# schematic.net
KiCad netlist of a schematic drawn in EasyEDA
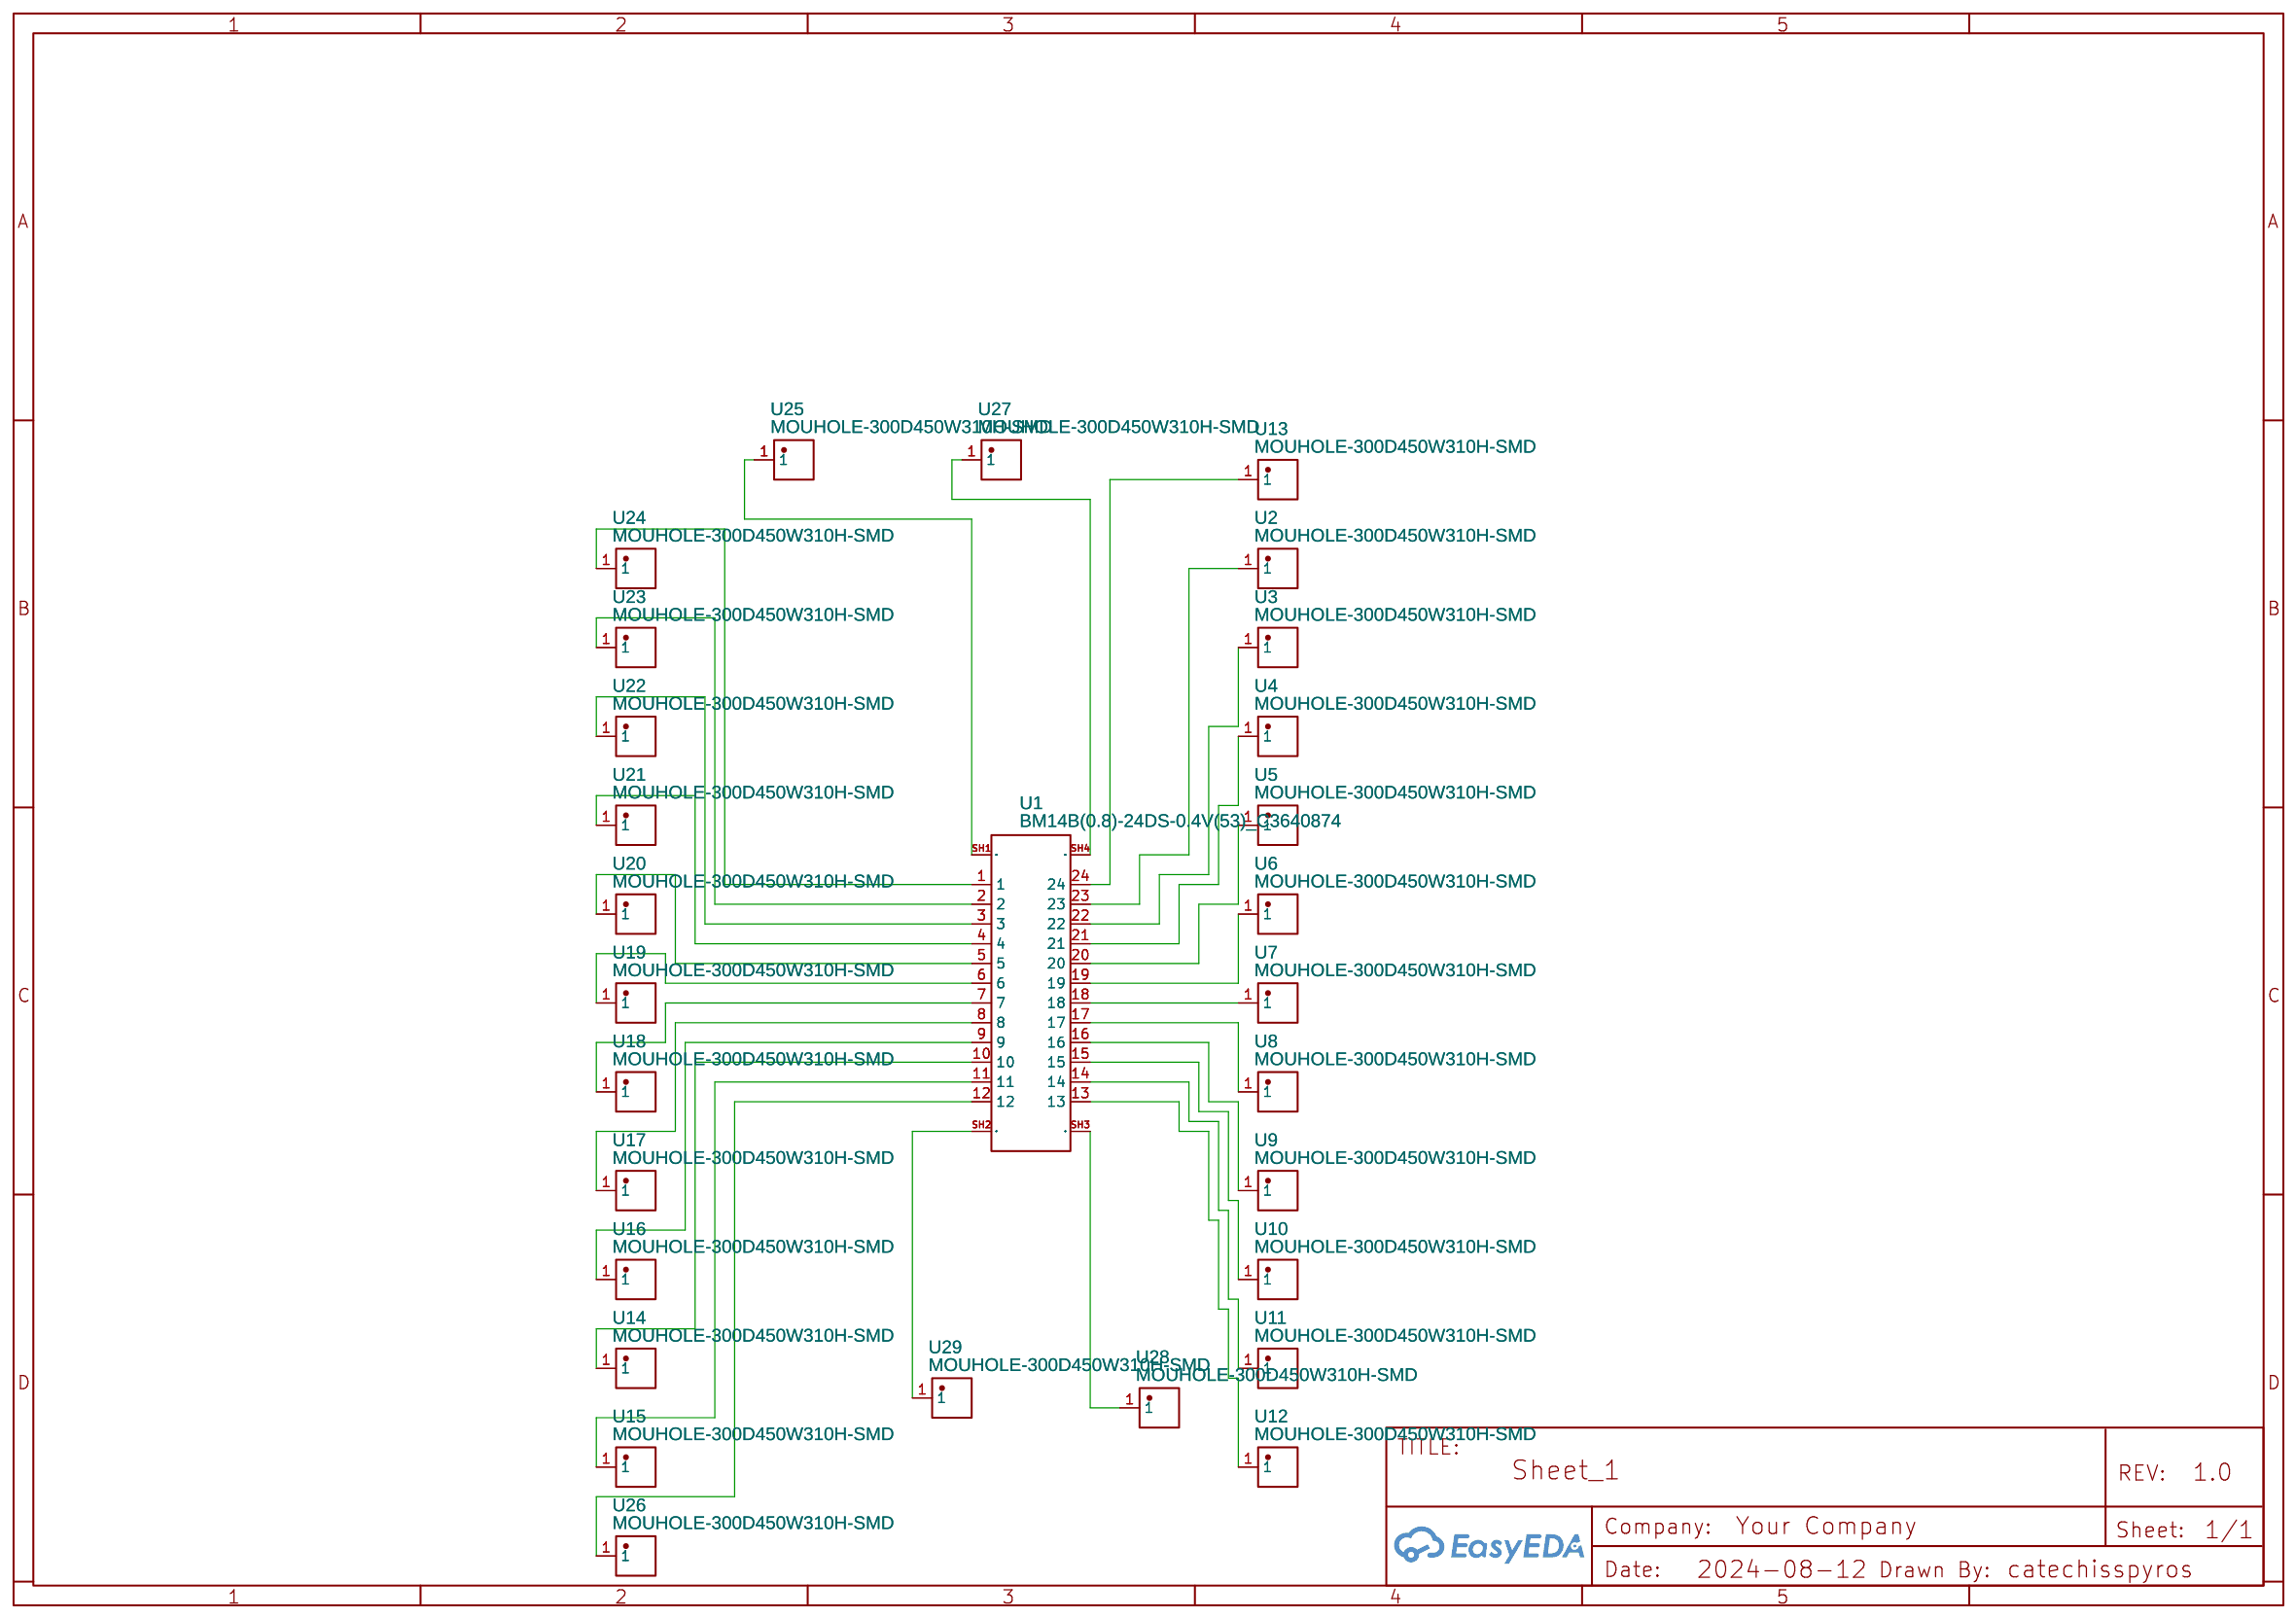
[diagram p0: schematic sheet]

(export (version "E")
  (design (tool "Eeschema 10.0.6"))
  (components
    (comp (ref "U1")
      (value "BM14B(0.8)-24DS-0.4V(53)_C3640874")
      (fields
        (field (name "Manufacturer Part") "BM14B(0.8)-24DS-0.4V(53)")
        (field (name "Manufacturer") "HRS(广濑)")
      )
      (libsource (lib "") (part "BM14B(0.8)-24DS-0.4V(53)_C3640874"))
    )
    (comp (ref "U2")
      (value "MOUHOLE-300D450W310H-SMD")
      (fields (field (name "Manufacturer Part") "MouHole-300D450W310H-SMD"))
      (libsource (lib "") (part "MOUHOLE-300D450W310H-SMD"))
    )
    (comp (ref "U3")
      (value "MOUHOLE-300D450W310H-SMD")
      (fields (field (name "Manufacturer Part") "MouHole-300D450W310H-SMD"))
      (libsource (lib "") (part "MOUHOLE-300D450W310H-SMD"))
    )
    (comp (ref "U4")
      (value "MOUHOLE-300D450W310H-SMD")
      (fields (field (name "Manufacturer Part") "MouHole-300D450W310H-SMD"))
      (libsource (lib "") (part "MOUHOLE-300D450W310H-SMD"))
    )
    (comp (ref "U5")
      (value "MOUHOLE-300D450W310H-SMD")
      (fields (field (name "Manufacturer Part") "MouHole-300D450W310H-SMD"))
      (libsource (lib "") (part "MOUHOLE-300D450W310H-SMD"))
    )
    (comp (ref "U6")
      (value "MOUHOLE-300D450W310H-SMD")
      (fields (field (name "Manufacturer Part") "MouHole-300D450W310H-SMD"))
      (libsource (lib "") (part "MOUHOLE-300D450W310H-SMD"))
    )
    (comp (ref "U7")
      (value "MOUHOLE-300D450W310H-SMD")
      (fields (field (name "Manufacturer Part") "MouHole-300D450W310H-SMD"))
      (libsource (lib "") (part "MOUHOLE-300D450W310H-SMD"))
    )
    (comp (ref "U8")
      (value "MOUHOLE-300D450W310H-SMD")
      (fields (field (name "Manufacturer Part") "MouHole-300D450W310H-SMD"))
      (libsource (lib "") (part "MOUHOLE-300D450W310H-SMD"))
    )
    (comp (ref "U9")
      (value "MOUHOLE-300D450W310H-SMD")
      (fields (field (name "Manufacturer Part") "MouHole-300D450W310H-SMD"))
      (libsource (lib "") (part "MOUHOLE-300D450W310H-SMD"))
    )
    (comp (ref "U10")
      (value "MOUHOLE-300D450W310H-SMD")
      (fields (field (name "Manufacturer Part") "MouHole-300D450W310H-SMD"))
      (libsource (lib "") (part "MOUHOLE-300D450W310H-SMD"))
    )
    (comp (ref "U11")
      (value "MOUHOLE-300D450W310H-SMD")
      (fields (field (name "Manufacturer Part") "MouHole-300D450W310H-SMD"))
      (libsource (lib "") (part "MOUHOLE-300D450W310H-SMD"))
    )
    (comp (ref "U12")
      (value "MOUHOLE-300D450W310H-SMD")
      (fields (field (name "Manufacturer Part") "MouHole-300D450W310H-SMD"))
      (libsource (lib "") (part "MOUHOLE-300D450W310H-SMD"))
    )
    (comp (ref "U13")
      (value "MOUHOLE-300D450W310H-SMD")
      (fields (field (name "Manufacturer Part") "MouHole-300D450W310H-SMD"))
      (libsource (lib "") (part "MOUHOLE-300D450W310H-SMD"))
    )
    (comp (ref "U14")
      (value "MOUHOLE-300D450W310H-SMD")
      (fields (field (name "Manufacturer Part") "MouHole-300D450W310H-SMD"))
      (libsource (lib "") (part "MOUHOLE-300D450W310H-SMD"))
    )
    (comp (ref "U15")
      (value "MOUHOLE-300D450W310H-SMD")
      (fields (field (name "Manufacturer Part") "MouHole-300D450W310H-SMD"))
      (libsource (lib "") (part "MOUHOLE-300D450W310H-SMD"))
    )
    (comp (ref "U16")
      (value "MOUHOLE-300D450W310H-SMD")
      (fields (field (name "Manufacturer Part") "MouHole-300D450W310H-SMD"))
      (libsource (lib "") (part "MOUHOLE-300D450W310H-SMD"))
    )
    (comp (ref "U17")
      (value "MOUHOLE-300D450W310H-SMD")
      (fields (field (name "Manufacturer Part") "MouHole-300D450W310H-SMD"))
      (libsource (lib "") (part "MOUHOLE-300D450W310H-SMD"))
    )
    (comp (ref "U18")
      (value "MOUHOLE-300D450W310H-SMD")
      (fields (field (name "Manufacturer Part") "MouHole-300D450W310H-SMD"))
      (libsource (lib "") (part "MOUHOLE-300D450W310H-SMD"))
    )
    (comp (ref "U19")
      (value "MOUHOLE-300D450W310H-SMD")
      (fields (field (name "Manufacturer Part") "MouHole-300D450W310H-SMD"))
      (libsource (lib "") (part "MOUHOLE-300D450W310H-SMD"))
    )
    (comp (ref "U20")
      (value "MOUHOLE-300D450W310H-SMD")
      (fields (field (name "Manufacturer Part") "MouHole-300D450W310H-SMD"))
      (libsource (lib "") (part "MOUHOLE-300D450W310H-SMD"))
    )
    (comp (ref "U21")
      (value "MOUHOLE-300D450W310H-SMD")
      (fields (field (name "Manufacturer Part") "MouHole-300D450W310H-SMD"))
      (libsource (lib "") (part "MOUHOLE-300D450W310H-SMD"))
    )
    (comp (ref "U22")
      (value "MOUHOLE-300D450W310H-SMD")
      (fields (field (name "Manufacturer Part") "MouHole-300D450W310H-SMD"))
      (libsource (lib "") (part "MOUHOLE-300D450W310H-SMD"))
    )
    (comp (ref "U23")
      (value "MOUHOLE-300D450W310H-SMD")
      (fields (field (name "Manufacturer Part") "MouHole-300D450W310H-SMD"))
      (libsource (lib "") (part "MOUHOLE-300D450W310H-SMD"))
    )
    (comp (ref "U24")
      (value "MOUHOLE-300D450W310H-SMD")
      (fields (field (name "Manufacturer Part") "MouHole-300D450W310H-SMD"))
      (libsource (lib "") (part "MOUHOLE-300D450W310H-SMD"))
    )
    (comp (ref "U25")
      (value "MOUHOLE-300D450W310H-SMD")
      (fields (field (name "Manufacturer Part") "MouHole-300D450W310H-SMD"))
      (libsource (lib "") (part "MOUHOLE-300D450W310H-SMD"))
    )
    (comp (ref "U26")
      (value "MOUHOLE-300D450W310H-SMD")
      (fields (field (name "Manufacturer Part") "MouHole-300D450W310H-SMD"))
      (libsource (lib "") (part "MOUHOLE-300D450W310H-SMD"))
    )
    (comp (ref "U27")
      (value "MOUHOLE-300D450W310H-SMD")
      (fields (field (name "Manufacturer Part") "MouHole-300D450W310H-SMD"))
      (libsource (lib "") (part "MOUHOLE-300D450W310H-SMD"))
    )
    (comp (ref "U28")
      (value "MOUHOLE-300D450W310H-SMD")
      (fields (field (name "Manufacturer Part") "MouHole-300D450W310H-SMD"))
      (libsource (lib "") (part "MOUHOLE-300D450W310H-SMD"))
    )
    (comp (ref "U29")
      (value "MOUHOLE-300D450W310H-SMD")
      (fields (field (name "Manufacturer Part") "MouHole-300D450W310H-SMD"))
      (libsource (lib "") (part "MOUHOLE-300D450W310H-SMD"))
    )
  )
  (nets
    (net (code "1") (name "Net-(U1-Pad1)") (class "Default")
      (node (ref "U1") (pin "1") (pinfunction "1_1") (pintype "unspecified"))
      (node (ref "U24") (pin "1") (pinfunction "1_1") (pintype "unspecified"))
    )
    (net (code "2") (name "Net-(U1-Pad2)") (class "Default")
      (node (ref "U1") (pin "2") (pinfunction "2_2") (pintype "unspecified"))
      (node (ref "U23") (pin "1") (pinfunction "1_1") (pintype "unspecified"))
    )
    (net (code "3") (name "Net-(U1-Pad3)") (class "Default")
      (node (ref "U1") (pin "3") (pinfunction "3_3") (pintype "unspecified"))
      (node (ref "U22") (pin "1") (pinfunction "1_1") (pintype "unspecified"))
    )
    (net (code "4") (name "Net-(U1-Pad4)") (class "Default")
      (node (ref "U1") (pin "4") (pinfunction "4_4") (pintype "unspecified"))
      (node (ref "U21") (pin "1") (pinfunction "1_1") (pintype "unspecified"))
    )
    (net (code "5") (name "Net-(U1-Pad5)") (class "Default")
      (node (ref "U1") (pin "5") (pinfunction "5_5") (pintype "unspecified"))
      (node (ref "U20") (pin "1") (pinfunction "1_1") (pintype "unspecified"))
    )
    (net (code "6") (name "Net-(U1-Pad6)") (class "Default")
      (node (ref "U1") (pin "6") (pinfunction "6_6") (pintype "unspecified"))
      (node (ref "U19") (pin "1") (pinfunction "1_1") (pintype "unspecified"))
    )
    (net (code "7") (name "Net-(U1-Pad7)") (class "Default")
      (node (ref "U1") (pin "7") (pinfunction "7_7") (pintype "unspecified"))
      (node (ref "U18") (pin "1") (pinfunction "1_1") (pintype "unspecified"))
    )
    (net (code "8") (name "Net-(U1-Pad8)") (class "Default")
      (node (ref "U1") (pin "8") (pinfunction "8_8") (pintype "unspecified"))
      (node (ref "U17") (pin "1") (pinfunction "1_1") (pintype "unspecified"))
    )
    (net (code "9") (name "Net-(U1-Pad9)") (class "Default")
      (node (ref "U1") (pin "9") (pinfunction "9_9") (pintype "unspecified"))
      (node (ref "U16") (pin "1") (pinfunction "1_1") (pintype "unspecified"))
    )
    (net (code "10") (name "Net-(U1-Pad10)") (class "Default")
      (node (ref "U1") (pin "10") (pinfunction "10_10") (pintype "unspecified"))
      (node (ref "U14") (pin "1") (pinfunction "1_1") (pintype "unspecified"))
    )
    (net (code "11") (name "Net-(U1-Pad11)") (class "Default")
      (node (ref "U1") (pin "11") (pinfunction "11_11") (pintype "unspecified"))
      (node (ref "U15") (pin "1") (pinfunction "1_1") (pintype "unspecified"))
    )
    (net (code "12") (name "Net-(U1-Pad12)") (class "Default")
      (node (ref "U1") (pin "12") (pinfunction "12_12") (pintype "unspecified"))
      (node (ref "U26") (pin "1") (pinfunction "1_1") (pintype "unspecified"))
    )
    (net (code "13") (name "Net-(U1-Pad13)") (class "Default")
      (node (ref "U1") (pin "13") (pinfunction "13_13") (pintype "unspecified"))
      (node (ref "U12") (pin "1") (pinfunction "1_1") (pintype "unspecified"))
    )
    (net (code "14") (name "Net-(U1-Pad14)") (class "Default")
      (node (ref "U1") (pin "14") (pinfunction "14_14") (pintype "unspecified"))
      (node (ref "U11") (pin "1") (pinfunction "1_1") (pintype "unspecified"))
    )
    (net (code "15") (name "Net-(U1-Pad15)") (class "Default")
      (node (ref "U1") (pin "15") (pinfunction "15_15") (pintype "unspecified"))
      (node (ref "U10") (pin "1") (pinfunction "1_1") (pintype "unspecified"))
    )
    (net (code "16") (name "Net-(U1-Pad16)") (class "Default")
      (node (ref "U1") (pin "16") (pinfunction "16_16") (pintype "unspecified"))
      (node (ref "U9") (pin "1") (pinfunction "1_1") (pintype "unspecified"))
    )
    (net (code "17") (name "Net-(U1-Pad17)") (class "Default")
      (node (ref "U1") (pin "17") (pinfunction "17_17") (pintype "unspecified"))
      (node (ref "U8") (pin "1") (pinfunction "1_1") (pintype "unspecified"))
    )
    (net (code "18") (name "Net-(U1-Pad18)") (class "Default")
      (node (ref "U1") (pin "18") (pinfunction "18_18") (pintype "unspecified"))
      (node (ref "U7") (pin "1") (pinfunction "1_1") (pintype "unspecified"))
    )
    (net (code "19") (name "Net-(U1-Pad19)") (class "Default")
      (node (ref "U1") (pin "19") (pinfunction "19_19") (pintype "unspecified"))
      (node (ref "U6") (pin "1") (pinfunction "1_1") (pintype "unspecified"))
    )
    (net (code "20") (name "Net-(U1-Pad20)") (class "Default")
      (node (ref "U1") (pin "20") (pinfunction "20_20") (pintype "unspecified"))
      (node (ref "U5") (pin "1") (pinfunction "1_1") (pintype "unspecified"))
    )
    (net (code "21") (name "Net-(U1-Pad21)") (class "Default")
      (node (ref "U1") (pin "21") (pinfunction "21_21") (pintype "unspecified"))
      (node (ref "U4") (pin "1") (pinfunction "1_1") (pintype "unspecified"))
    )
    (net (code "22") (name "Net-(U1-Pad22)") (class "Default")
      (node (ref "U1") (pin "22") (pinfunction "22_22") (pintype "unspecified"))
      (node (ref "U3") (pin "1") (pinfunction "1_1") (pintype "unspecified"))
    )
    (net (code "23") (name "Net-(U1-Pad23)") (class "Default")
      (node (ref "U1") (pin "23") (pinfunction "23_23") (pintype "unspecified"))
      (node (ref "U2") (pin "1") (pinfunction "1_1") (pintype "unspecified"))
    )
    (net (code "24") (name "Net-(U1-Pad24)") (class "Default")
      (node (ref "U1") (pin "24") (pinfunction "24_24") (pintype "unspecified"))
      (node (ref "U13") (pin "1") (pinfunction "1_1") (pintype "unspecified"))
    )
    (net (code "25") (name "Net-(U1-PadSH1)") (class "Default")
      (node (ref "U1") (pin "SH1") (pinfunction "SH1_SH1") (pintype "unspecified"))
      (node (ref "U25") (pin "1") (pinfunction "1_1") (pintype "unspecified"))
    )
    (net (code "26") (name "Net-(U1-PadSH2)") (class "Default")
      (node (ref "U1") (pin "SH2") (pinfunction "SH2_SH2") (pintype "unspecified"))
      (node (ref "U29") (pin "1") (pinfunction "1_1") (pintype "unspecified"))
    )
    (net (code "27") (name "Net-(U1-PadSH3)") (class "Default")
      (node (ref "U1") (pin "SH3") (pinfunction "SH3_SH3") (pintype "unspecified"))
      (node (ref "U28") (pin "1") (pinfunction "1_1") (pintype "unspecified"))
    )
    (net (code "28") (name "Net-(U1-PadSH4)") (class "Default")
      (node (ref "U1") (pin "SH4") (pinfunction "SH4_SH4") (pintype "unspecified"))
      (node (ref "U27") (pin "1") (pinfunction "1_1") (pintype "unspecified"))
    )
  )
)
